# 5vDC.net
KiCad netlist of a schematic drawn in EAGLE
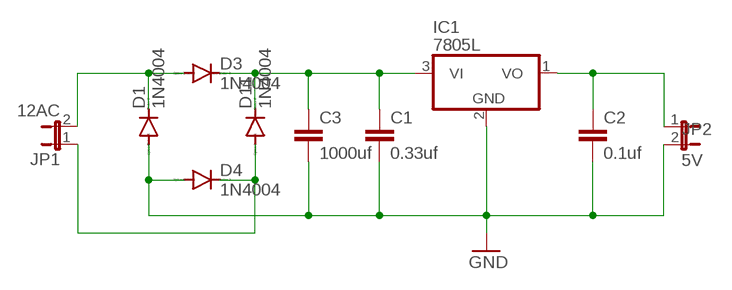
[diagram p0: schematic, sheet 1]

(export (version "E")
  (design (tool "Eeschema 10.0.6"))
  (components
    (comp (ref "C1")
      (value "0.33uf")
      (footprint "eagle-import:C2.5-3")
      (libsource (lib "eagle-import") (part "C2,5-3"))
    )
    (comp (ref "C2")
      (value "0.1uf")
      (footprint "eagle-import:C2.5-3")
      (libsource (lib "eagle-import") (part "C2,5-3"))
    )
    (comp (ref "C3")
      (value "1000uf")
      (footprint "eagle-import:C2.5-3")
      (libsource (lib "eagle-import") (part "C2,5-3"))
    )
    (comp (ref "D1")
      (value "1N4004")
      (footprint "eagle-import:DO41-10")
      (libsource (lib "eagle-import") (part "1N4004"))
    )
    (comp (ref "D3")
      (value "1N4004")
      (footprint "eagle-import:DO41-10")
      (libsource (lib "eagle-import") (part "1N4004"))
    )
    (comp (ref "D4")
      (value "1N4004")
      (footprint "eagle-import:DO41-10")
      (libsource (lib "eagle-import") (part "1N4004"))
    )
    (comp (ref "D11")
      (value "1N4004")
      (footprint "eagle-import:DO41-10")
      (libsource (lib "eagle-import") (part "1N4004"))
    )
    (comp (ref "IC1")
      (value "7805L")
      (footprint "eagle-import:TO92")
      (libsource (lib "eagle-import") (part "78L05"))
    )
    (comp (ref "JP1")
      (value "12AC")
      (footprint "eagle-import:JP1")
      (libsource (lib "eagle-import") (part "JP1E"))
    )
    (comp (ref "JP2")
      (value "5V")
      (footprint "eagle-import:JP1")
      (libsource (lib "eagle-import") (part "JP1E"))
    )
  )
  (nets
    (net (code "1") (name "GND") (class "Default")
      (node (ref "C1") (pin "2") (pinfunction "2_2") (pintype "passive"))
      (node (ref "C2") (pin "2") (pinfunction "2_2") (pintype "passive"))
      (node (ref "C3") (pin "2") (pinfunction "2_2") (pintype "passive"))
      (node (ref "D1") (pin "A") (pinfunction "A_A") (pintype "passive"))
      (node (ref "D4") (pin "A") (pinfunction "A_A") (pintype "passive"))
      (node (ref "IC1") (pin "2") (pinfunction "GND_2") (pintype "passive"))
      (node (ref "JP2") (pin "2") (pinfunction "2_2") (pintype "passive"))
    )
    (net (code "2") (name "Net-(D1-PadC)") (class "Default")
      (node (ref "D1") (pin "C") (pinfunction "C_C") (pintype "passive"))
      (node (ref "D3") (pin "A") (pinfunction "A_A") (pintype "passive"))
      (node (ref "JP1") (pin "2") (pinfunction "2_2") (pintype "passive"))
    )
    (net (code "3") (name "Net-(D11-PadA)") (class "Default")
      (node (ref "D11") (pin "A") (pinfunction "A_A") (pintype "passive"))
      (node (ref "D4") (pin "C") (pinfunction "C_C") (pintype "passive"))
      (node (ref "JP1") (pin "1") (pinfunction "1_1") (pintype "passive"))
    )
    (net (code "4") (name "Net-(IC1-VI)") (class "Default")
      (node (ref "C1") (pin "1") (pinfunction "1_1") (pintype "passive"))
      (node (ref "C3") (pin "1") (pinfunction "1_1") (pintype "passive"))
      (node (ref "D11") (pin "C") (pinfunction "C_C") (pintype "passive"))
      (node (ref "D3") (pin "C") (pinfunction "C_C") (pintype "passive"))
      (node (ref "IC1") (pin "3") (pinfunction "VI_3") (pintype "input"))
    )
    (net (code "5") (name "Net-(IC1-VO)") (class "Default")
      (node (ref "C2") (pin "1") (pinfunction "1_1") (pintype "passive"))
      (node (ref "IC1") (pin "1") (pinfunction "VO_1") (pintype "passive"))
      (node (ref "JP2") (pin "1") (pinfunction "1_1") (pintype "passive"))
    )
  )
)
